# SCH_Do_an1_2023-05-08.net
KiCad netlist of a schematic drawn in EasyEDA
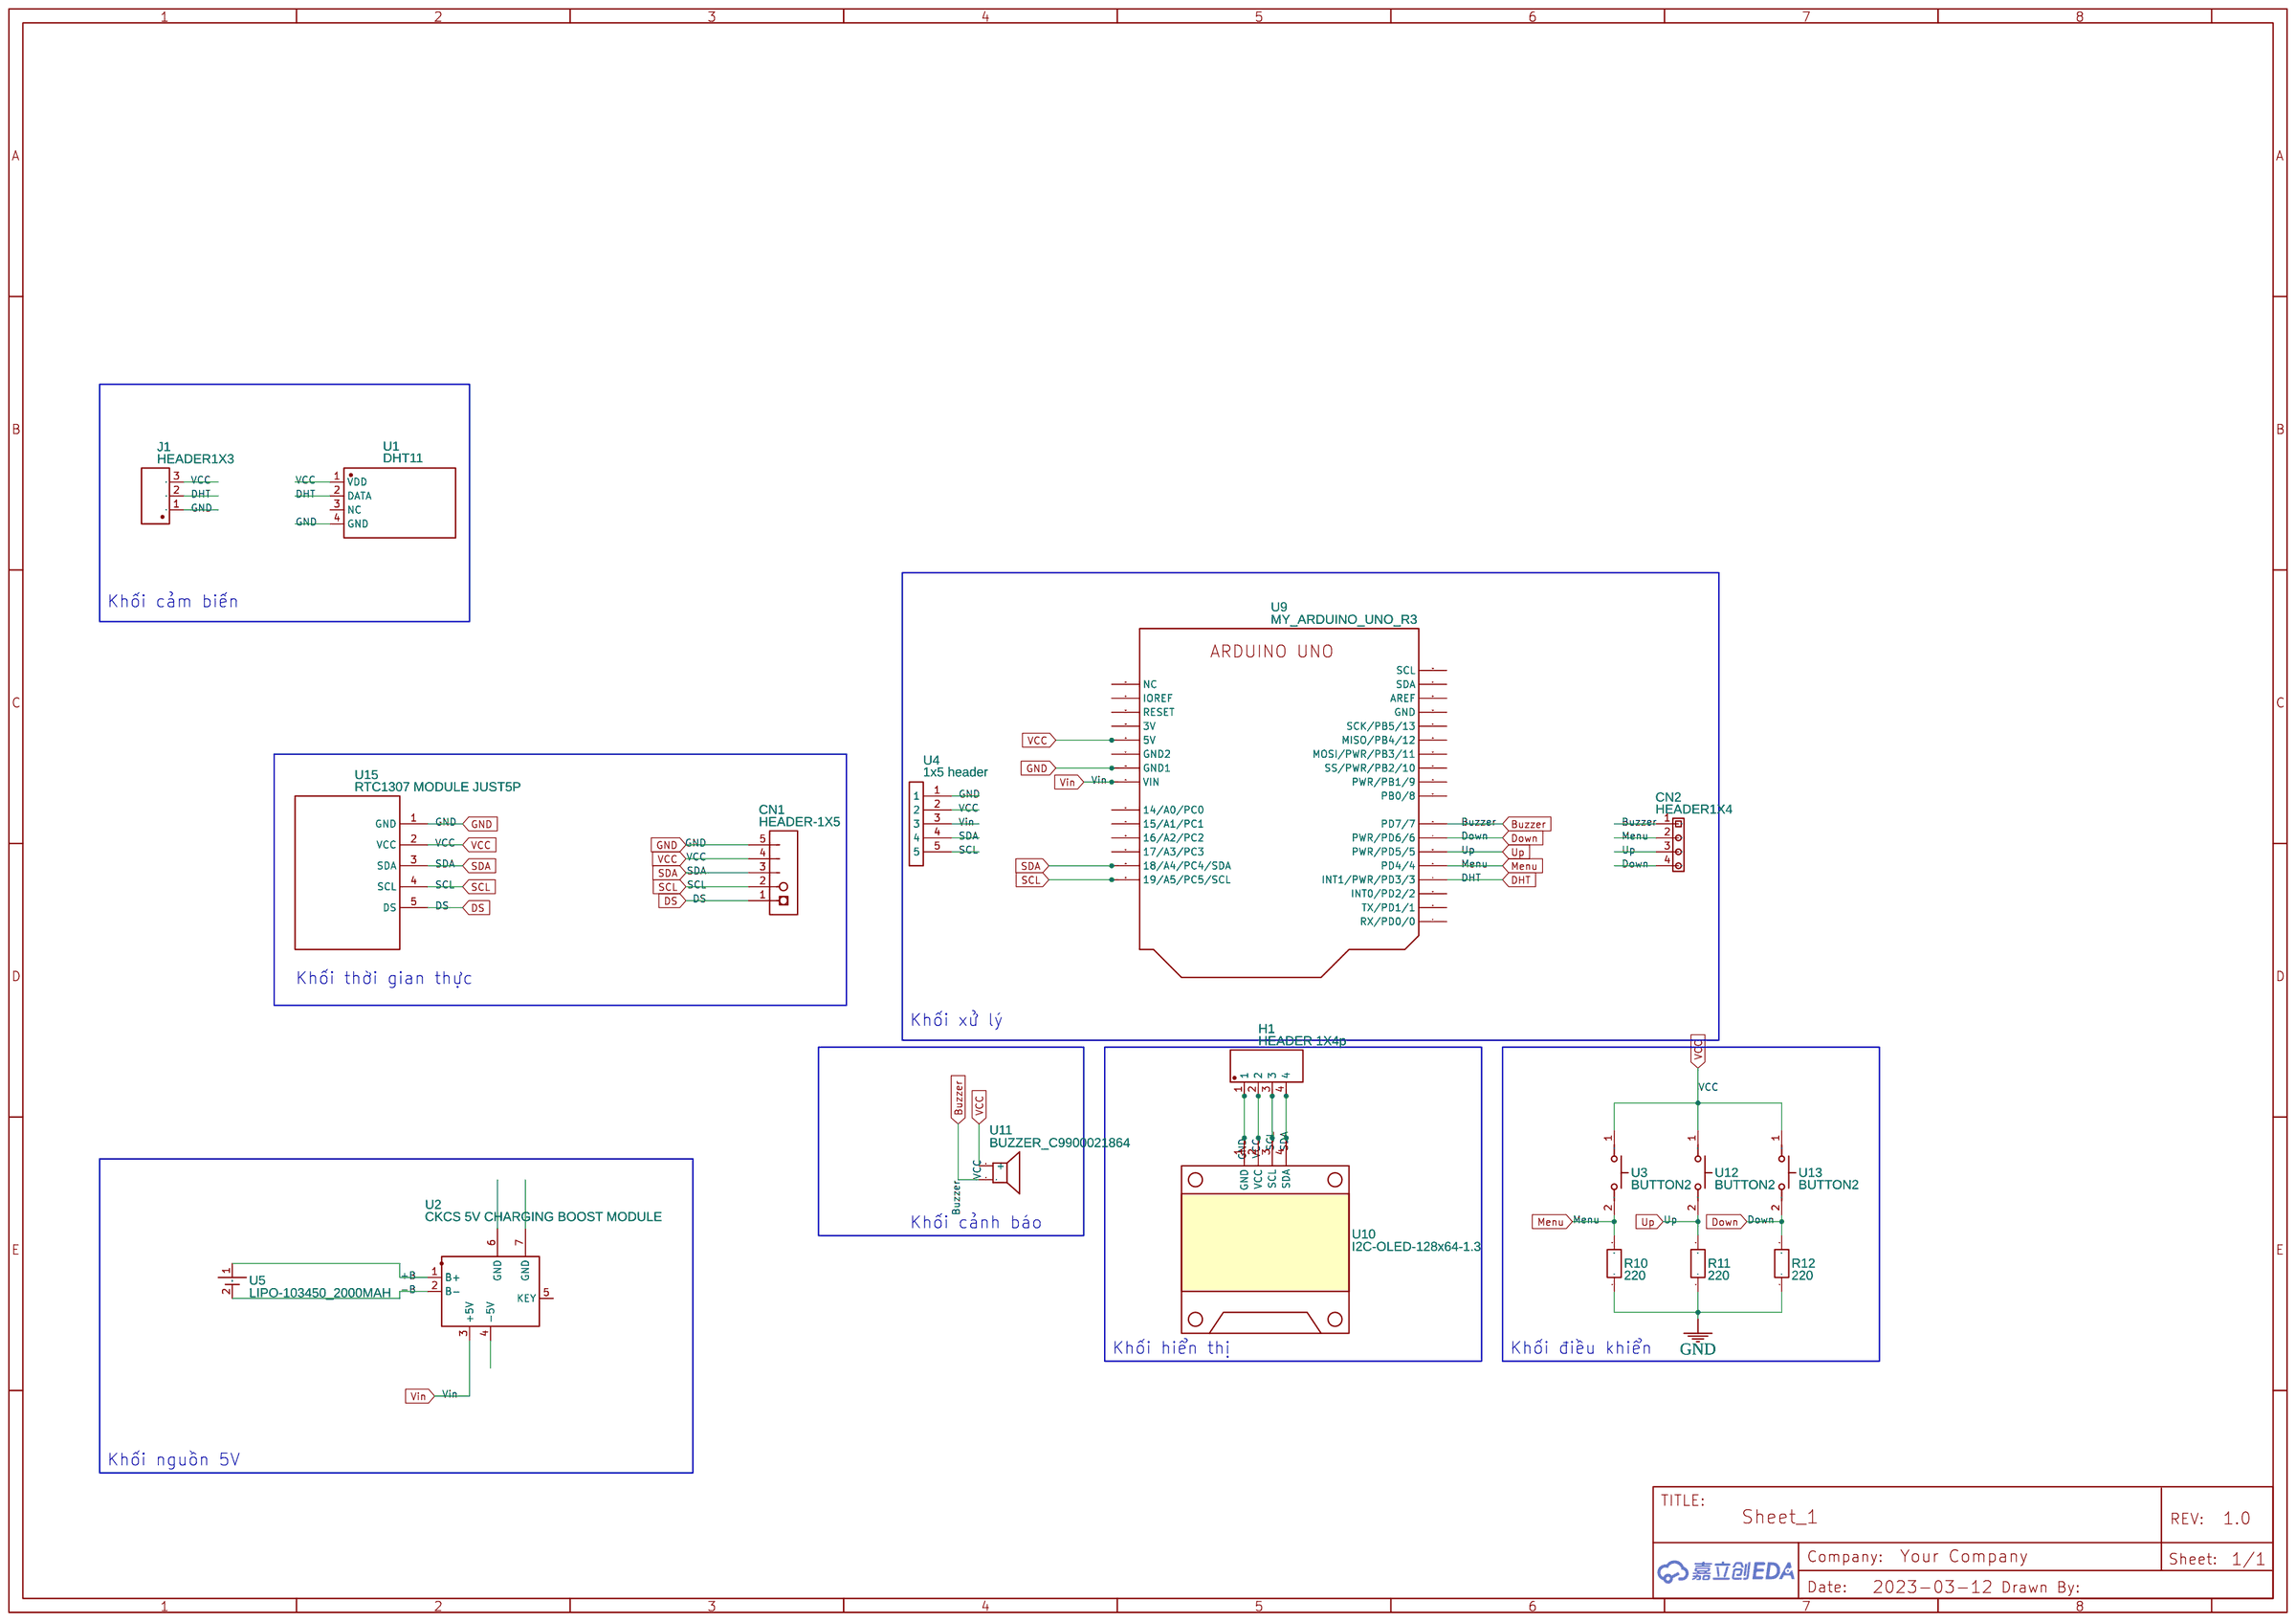
[diagram p0: schematic sheet]

(export (version "E")
  (design (tool "Eeschema 10.0.6"))
  (components
    (comp (ref "CN1") (value "HEADER-1X5") (libsource (lib "") (part "HEADER-1X5")))
    (comp (ref "CN2") (value "HEADER1X4") (libsource (lib "") (part "HEADER1X4")))
    (comp (ref "H1") (value "HEADER 1X4p") (libsource (lib "") (part "HEADER 1X4p")))
    (comp (ref "J1") (value "HEADER1X3") (libsource (lib "") (part "HEADER1X3")))
    (comp (ref "R10") (value "220") (libsource (lib "") (part "R_0603_EU")))
    (comp (ref "R11") (value "220") (libsource (lib "") (part "R_0603_EU")))
    (comp (ref "R12") (value "220") (libsource (lib "") (part "R_0603_EU")))
    (comp (ref "U1")
      (value "DHT11")
      (fields (field (name "BOM_Supplier Part") "C117051"))
      (libsource (lib "") (part "DHT11"))
    )
    (comp (ref "U2")
      (value "CKCS 5V CHARGING BOOST MODULE")
      (libsource (lib "") (part "CKCS 5V CHARGING BOOST MODULE"))
    )
    (comp (ref "U3")
      (value "BUTTON2")
      (fields (field (name "BOM_Supplier Part") "C9900005988"))
      (libsource (lib "") (part "BUTTON2"))
    )
    (comp (ref "U4") (value "1x5 header") (libsource (lib "") (part "1x5 header")))
    (comp (ref "U5") (value "LIPO-103450_2000MAH") (libsource (lib "") (part "LIPO-103450_2000MAH")))
    (comp (ref "U9") (value "MY_ARDUINO_UNO_R3") (libsource (lib "") (part "MY_ARDUINO_UNO_R3")))
    (comp (ref "U10") (value "I2C-OLED-128x64-1.3") (libsource (lib "") (part "I2C-OLED-128x64-1.3")))
    (comp (ref "U11")
      (value "BUZZER_C9900021864")
      (fields
        (field (name "BOM_Manufacturer Part") "BUZZER")
        (field (name "BOM_Supplier Part") "C9900021864")
      )
      (libsource (lib "") (part "BUZZER_C9900021864"))
    )
    (comp (ref "U12")
      (value "BUTTON2")
      (fields (field (name "BOM_Supplier Part") "C9900005988"))
      (libsource (lib "") (part "BUTTON2"))
    )
    (comp (ref "U13")
      (value "BUTTON2")
      (fields (field (name "BOM_Supplier Part") "C9900005988"))
      (libsource (lib "") (part "BUTTON2"))
    )
    (comp (ref "U15") (value "RTC1307 MODULE JUST5P") (libsource (lib "") (part "RTC1307 MODULE JUST5P")))
  )
  (nets
    (net (code "1") (name "/+B") (class "Default")
      (node (ref "U2") (pin "1") (pinfunction "B+_1") (pintype "unspecified"))
      (node (ref "U5") (pin "1") (pinfunction "POS_1") (pintype "unspecified"))
    )
    (net (code "2") (name "/-B") (class "Default")
      (node (ref "U2") (pin "2") (pinfunction "B-_2") (pintype "unspecified"))
      (node (ref "U5") (pin "2") (pinfunction "POS_2") (pintype "unspecified"))
    )
    (net (code "3") (name "Buzzer") (class "Default")
      (node (ref "CN2") (pin "1") (pinfunction "1_1") (pintype "unspecified"))
      (node (ref "U11") (pin "1") (pinfunction "1_1") (pintype "unspecified"))
      (node (ref "U9") (pin "8") (pinfunction "PD7/7_8") (pintype "unspecified"))
    )
    (net (code "4") (name "DHT") (class "Default")
      (node (ref "J1") (pin "2") (pinfunction "2_2") (pintype "unspecified"))
      (node (ref "U1") (pin "2") (pinfunction "DATA_2") (pintype "unspecified"))
      (node (ref "U9") (pin "4") (pinfunction "INT1/PWR/PD3/3_4") (pintype "unspecified"))
    )
    (net (code "5") (name "DS") (class "Default")
      (node (ref "CN1") (pin "1") (pintype "unspecified"))
      (node (ref "U15") (pin "5") (pinfunction "DS_5") (pintype "unspecified"))
    )
    (net (code "6") (name "Down") (class "Default")
      (node (ref "CN2") (pin "4") (pinfunction "4_4") (pintype "unspecified"))
      (node (ref "R12") (pin "2") (pinfunction "2_2") (pintype "unspecified"))
      (node (ref "U13") (pin "2") (pinfunction "2_2") (pintype "unspecified"))
      (node (ref "U9") (pin "7") (pinfunction "PWR/PD6/6_7") (pintype "unspecified"))
    )
    (net (code "7") (name "GND") (class "Default")
      (node (ref "CN1") (pin "5") (pintype "unspecified"))
      (node (ref "H1") (pin "1") (pinfunction "1_1") (pintype "unspecified"))
      (node (ref "J1") (pin "1") (pinfunction "1_1") (pintype "unspecified"))
      (node (ref "R10") (pin "1") (pinfunction "1_1") (pintype "unspecified"))
      (node (ref "R11") (pin "1") (pinfunction "1_1") (pintype "unspecified"))
      (node (ref "R12") (pin "1") (pinfunction "1_1") (pintype "unspecified"))
      (node (ref "U1") (pin "4") (pinfunction "GND_4") (pintype "unspecified"))
      (node (ref "U10") (pin "1") (pinfunction "GND_1") (pintype "unspecified"))
      (node (ref "U15") (pin "1") (pinfunction "GND_1") (pintype "unspecified"))
      (node (ref "U4") (pin "1") (pinfunction "1_1") (pintype "unspecified"))
      (node (ref "U9") (pin "26") (pinfunction "GND1_26") (pintype "passive"))
    )
    (net (code "8") (name "Menu") (class "Default")
      (node (ref "CN2") (pin "2") (pinfunction "2_2") (pintype "unspecified"))
      (node (ref "R10") (pin "2") (pinfunction "2_2") (pintype "unspecified"))
      (node (ref "U3") (pin "2") (pinfunction "2_2") (pintype "unspecified"))
      (node (ref "U9") (pin "5") (pinfunction "PD4/4_5") (pintype "unspecified"))
    )
    (net (code "9") (name "SCL") (class "Default")
      (node (ref "CN1") (pin "2") (pintype "unspecified"))
      (node (ref "H1") (pin "3") (pinfunction "3_3") (pintype "unspecified"))
      (node (ref "U10") (pin "3") (pinfunction "SCL_3") (pintype "bidirectional"))
      (node (ref "U15") (pin "4") (pinfunction "SCL_4") (pintype "unspecified"))
      (node (ref "U4") (pin "5") (pinfunction "5_5") (pintype "unspecified"))
      (node (ref "U9") (pin "19") (pinfunction "19/A5/PC5/SCL_19") (pintype "unspecified"))
    )
    (net (code "10") (name "SDA") (class "Default")
      (node (ref "CN1") (pin "3") (pintype "unspecified"))
      (node (ref "H1") (pin "4") (pinfunction "4_4") (pintype "unspecified"))
      (node (ref "U10") (pin "4") (pinfunction "SDA_4") (pintype "bidirectional"))
      (node (ref "U15") (pin "3") (pinfunction "SDA_3") (pintype "unspecified"))
      (node (ref "U4") (pin "4") (pinfunction "4_4") (pintype "unspecified"))
      (node (ref "U9") (pin "20") (pinfunction "18/A4/PC4/SDA_20") (pintype "unspecified"))
    )
    (net (code "11") (name "Up") (class "Default")
      (node (ref "CN2") (pin "3") (pinfunction "3_3") (pintype "unspecified"))
      (node (ref "R11") (pin "2") (pinfunction "2_2") (pintype "unspecified"))
      (node (ref "U12") (pin "2") (pinfunction "2_2") (pintype "unspecified"))
      (node (ref "U9") (pin "6") (pinfunction "PWR/PD5/5_6") (pintype "unspecified"))
    )
    (net (code "12") (name "VCC") (class "Default")
      (node (ref "CN1") (pin "4") (pintype "unspecified"))
      (node (ref "H1") (pin "2") (pinfunction "2_2") (pintype "unspecified"))
      (node (ref "J1") (pin "3") (pinfunction "3_3") (pintype "unspecified"))
      (node (ref "U1") (pin "1") (pinfunction "VDD_1") (pintype "unspecified"))
      (node (ref "U10") (pin "2") (pinfunction "VCC_2") (pintype "passive"))
      (node (ref "U11") (pin "2") (pinfunction "+_2") (pintype "unspecified"))
      (node (ref "U12") (pin "1") (pinfunction "1_1") (pintype "unspecified"))
      (node (ref "U13") (pin "1") (pinfunction "1_1") (pintype "unspecified"))
      (node (ref "U15") (pin "2") (pinfunction "VCC_2") (pintype "unspecified"))
      (node (ref "U3") (pin "1") (pinfunction "1_1") (pintype "unspecified"))
      (node (ref "U4") (pin "2") (pinfunction "2_2") (pintype "unspecified"))
      (node (ref "U9") (pin "28") (pinfunction "5V_28") (pintype "passive"))
    )
    (net (code "13") (name "Vin") (class "Default")
      (node (ref "U2") (pin "3") (pinfunction "+5V_3") (pintype "unspecified"))
      (node (ref "U4") (pin "3") (pinfunction "3_3") (pintype "unspecified"))
      (node (ref "U9") (pin "25") (pinfunction "VIN_25") (pintype "passive"))
    )
    (net (code "14") (name "unconnected-(U1-NC-Pad3)") (class "Default")
      (node (ref "U1") (pin "3") (pinfunction "NC_3") (pintype "unspecified"))
    )
    (net (code "15") (name "unconnected-(U2--5V-Pad4)") (class "Default")
      (node (ref "U2") (pin "4") (pinfunction "-5V_4") (pintype "unspecified"))
    )
    (net (code "16") (name "unconnected-(U2-GND-Pad6)") (class "Default")
      (node (ref "U2") (pin "6") (pinfunction "GND_6") (pintype "unspecified"))
    )
    (net (code "17") (name "unconnected-(U2-GND-Pad7)") (class "Default")
      (node (ref "U2") (pin "7") (pinfunction "GND_7") (pintype "unspecified"))
    )
    (net (code "18") (name "unconnected-(U2-KEY-Pad5)") (class "Default")
      (node (ref "U2") (pin "5") (pinfunction "KEY_5") (pintype "unspecified"))
    )
    (net (code "19") (name "unconnected-(U9-3V-Pad29)") (class "Default")
      (node (ref "U9") (pin "29") (pinfunction "3V_29") (pintype "passive"))
    )
    (net (code "20") (name "unconnected-(U9-14{slash}A0{slash}PC0-Pad24)") (class "Default")
      (node (ref "U9") (pin "24") (pinfunction "14/A0/PC0_24") (pintype "unspecified"))
    )
    (net (code "21") (name "unconnected-(U9-15{slash}A1{slash}PC1-Pad23)") (class "Default")
      (node (ref "U9") (pin "23") (pinfunction "15/A1/PC1_23") (pintype "unspecified"))
    )
    (net (code "22") (name "unconnected-(U9-16{slash}A2{slash}PC2-Pad22)") (class "Default")
      (node (ref "U9") (pin "22") (pinfunction "16/A2/PC2_22") (pintype "unspecified"))
    )
    (net (code "23") (name "unconnected-(U9-17{slash}A3{slash}PC3-Pad21)") (class "Default")
      (node (ref "U9") (pin "21") (pinfunction "17/A3/PC3_21") (pintype "unspecified"))
    )
    (net (code "24") (name "unconnected-(U9-AREF-Pad16)") (class "Default")
      (node (ref "U9") (pin "16") (pinfunction "AREF_16") (pintype "unspecified"))
    )
    (net (code "25") (name "unconnected-(U9-GND-Pad15)") (class "Default")
      (node (ref "U9") (pin "15") (pinfunction "GND_15") (pintype "passive"))
    )
    (net (code "26") (name "unconnected-(U9-GND2-Pad27)") (class "Default")
      (node (ref "U9") (pin "27") (pinfunction "GND2_27") (pintype "passive"))
    )
    (net (code "27") (name "unconnected-(U9-INT0{slash}PD2{slash}2-Pad3)") (class "Default")
      (node (ref "U9") (pin "3") (pinfunction "INT0/PD2/2_3") (pintype "unspecified"))
    )
    (net (code "28") (name "unconnected-(U9-IOREF-Pad31)") (class "Default")
      (node (ref "U9") (pin "31") (pinfunction "IOREF_31") (pintype "unspecified"))
    )
    (net (code "29") (name "unconnected-(U9-MISO{slash}PB4{slash}12-Pad13)") (class "Default")
      (node (ref "U9") (pin "13") (pinfunction "MISO/PB4/12_13") (pintype "unspecified"))
    )
    (net (code "30") (name "unconnected-(U9-MOSI{slash}PWR{slash}PB3{slash}11-Pad12)") (class "Default")
      (node (ref "U9") (pin "12") (pinfunction "MOSI/PWR/PB3/11_12") (pintype "unspecified"))
    )
    (net (code "31") (name "unconnected-(U9-NC-Pad32)") (class "Default")
      (node (ref "U9") (pin "32") (pinfunction "NC_32") (pintype "unspecified"))
    )
    (net (code "32") (name "unconnected-(U9-PB0{slash}8-Pad9)") (class "Default")
      (node (ref "U9") (pin "9") (pinfunction "PB0/8_9") (pintype "unspecified"))
    )
    (net (code "33") (name "unconnected-(U9-PWR{slash}PB1{slash}9-Pad10)") (class "Default")
      (node (ref "U9") (pin "10") (pinfunction "PWR/PB1/9_10") (pintype "unspecified"))
    )
    (net (code "34") (name "unconnected-(U9-RESET-Pad30)") (class "Default")
      (node (ref "U9") (pin "30") (pinfunction "RESET_30") (pintype "unspecified"))
    )
    (net (code "35") (name "unconnected-(U9-RX{slash}PD0{slash}0-Pad1)") (class "Default")
      (node (ref "U9") (pin "1") (pinfunction "RX/PD0/0_1") (pintype "unspecified"))
    )
    (net (code "36") (name "unconnected-(U9-SCK{slash}PB5{slash}13-Pad14)") (class "Default")
      (node (ref "U9") (pin "14") (pinfunction "SCK/PB5/13_14") (pintype "unspecified"))
    )
    (net (code "37") (name "unconnected-(U9-SCL-Pad18)") (class "Default")
      (node (ref "U9") (pin "18") (pinfunction "SCL_18") (pintype "unspecified"))
    )
    (net (code "38") (name "unconnected-(U9-SDA-Pad17)") (class "Default")
      (node (ref "U9") (pin "17") (pinfunction "SDA_17") (pintype "unspecified"))
    )
    (net (code "39") (name "unconnected-(U9-SS{slash}PWR{slash}PB2{slash}10-Pad11)") (class "Default")
      (node (ref "U9") (pin "11") (pinfunction "SS/PWR/PB2/10_11") (pintype "unspecified"))
    )
    (net (code "40") (name "unconnected-(U9-TX{slash}PD1{slash}1-Pad2)") (class "Default")
      (node (ref "U9") (pin "2") (pinfunction "TX/PD1/1_2") (pintype "unspecified"))
    )
  )
)
